# 70MHz_DDS_generator.net
KiCad netlist of a schematic drawn in EAGLE
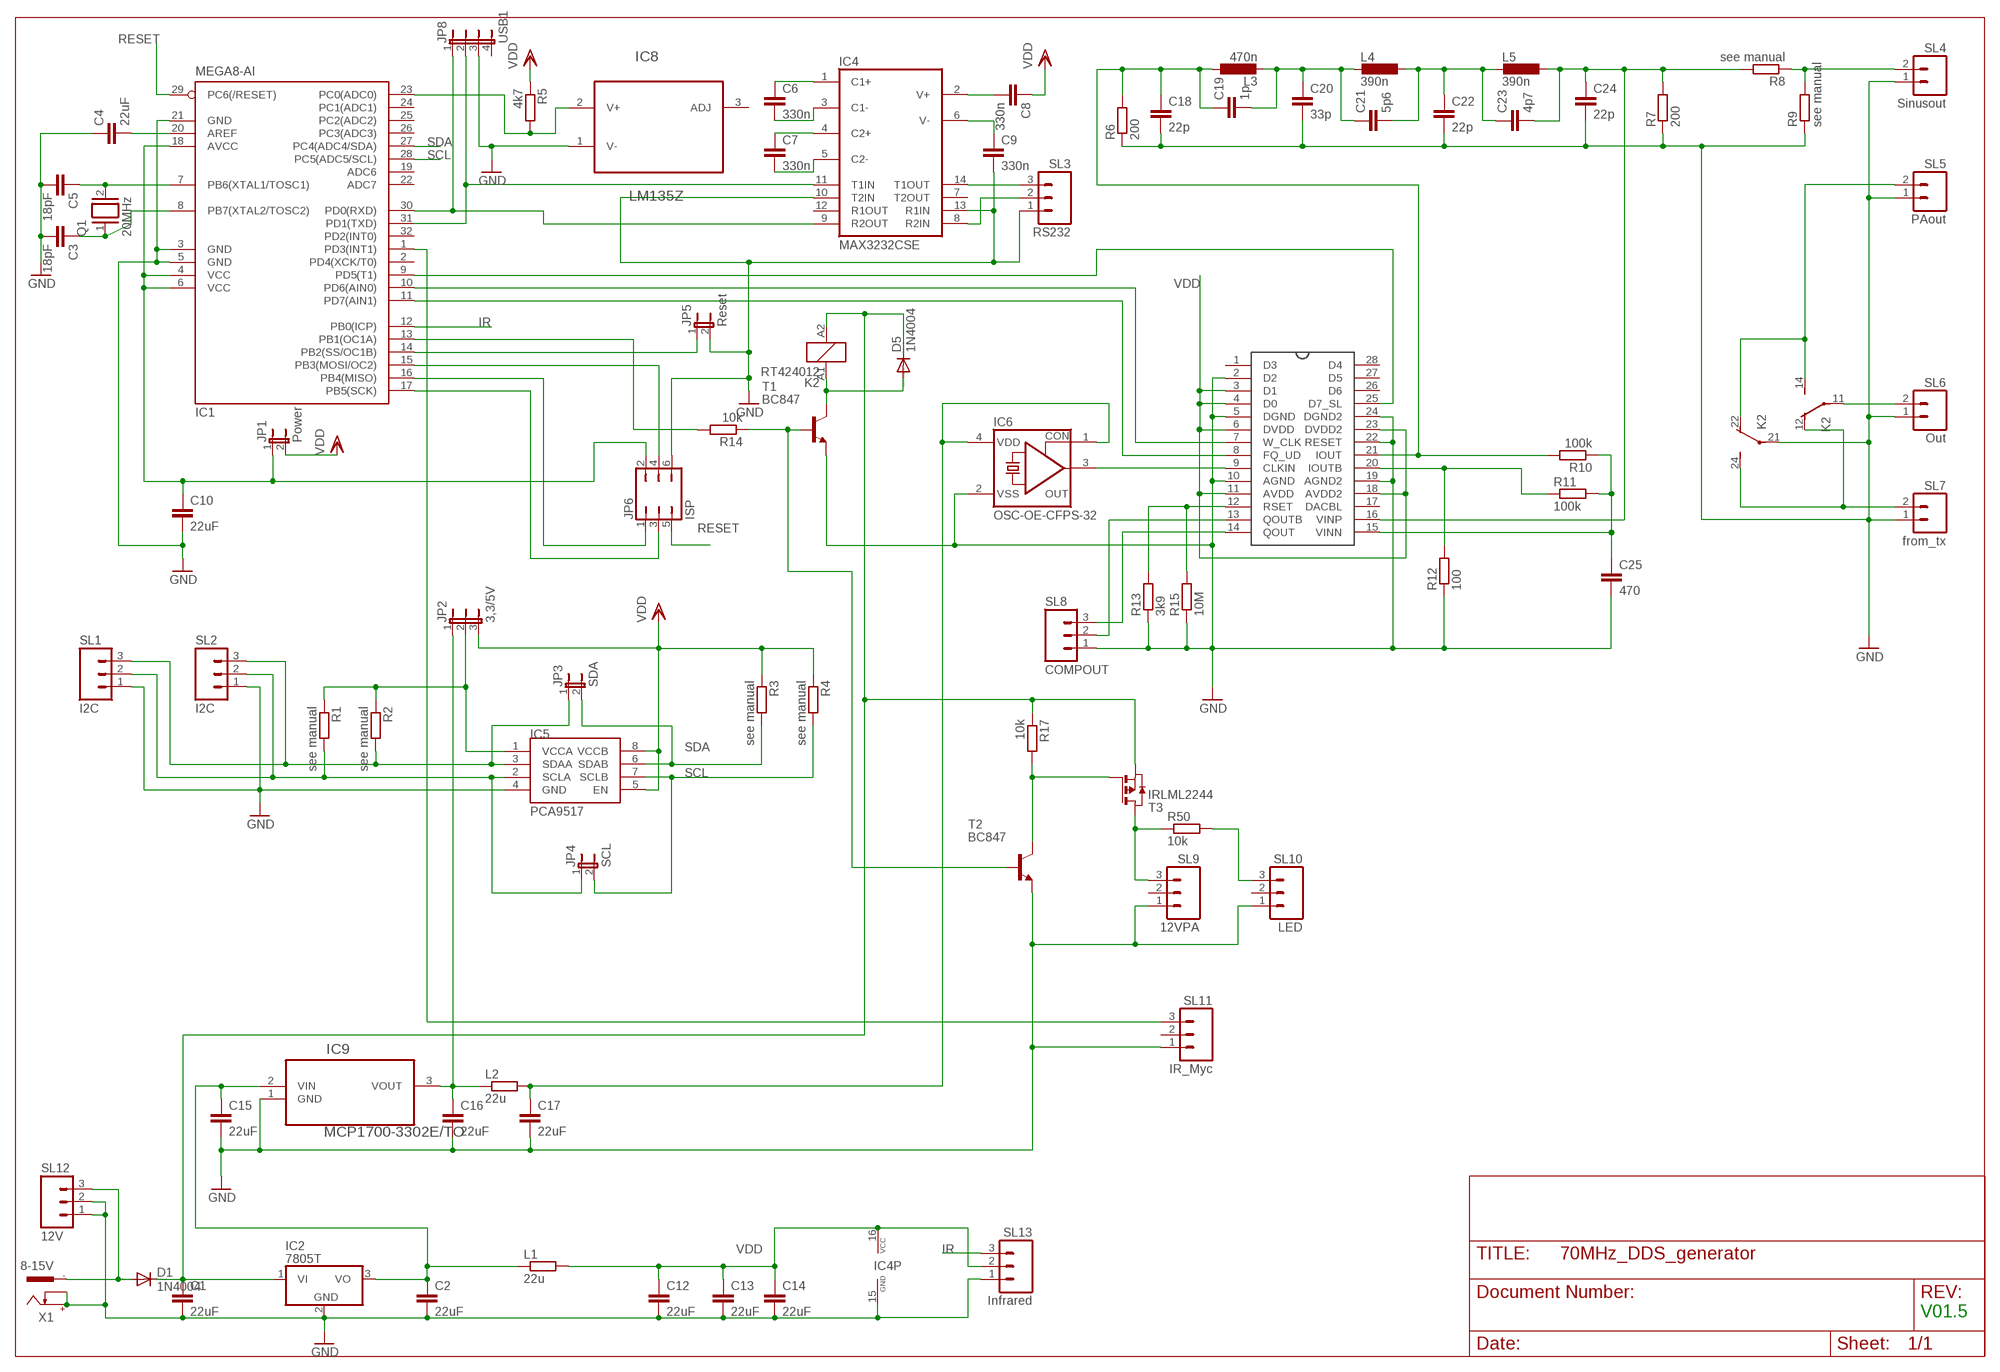
[diagram p0: schematic, sheet 1]

(export (version "E")
  (design (tool "Eeschema 10.0.6"))
  (components
    (comp (ref "C1")
      (value "22uF")
      (footprint "eagle-import:C1206")
      (libsource (lib "eagle-import") (part "C-EUC1206"))
    )
    (comp (ref "C2")
      (value "22uF")
      (footprint "eagle-import:C1206")
      (libsource (lib "eagle-import") (part "C-EUC1206"))
    )
    (comp (ref "C3")
      (value "18pF")
      (footprint "eagle-import:C025-025X050")
      (libsource (lib "eagle-import") (part "resistor_C-EU025-025X050"))
    )
    (comp (ref "C4")
      (value "22uF")
      (footprint "eagle-import:C1206")
      (libsource (lib "eagle-import") (part "C-EUC1206"))
    )
    (comp (ref "C5")
      (value "18pF")
      (footprint "eagle-import:C025-025X050")
      (libsource (lib "eagle-import") (part "resistor_C-EU025-025X050"))
    )
    (comp (ref "C6")
      (value "330n")
      (footprint "eagle-import:C1206")
      (libsource (lib "eagle-import") (part "C-EUC1206"))
    )
    (comp (ref "C7")
      (value "330n")
      (footprint "eagle-import:C1206")
      (libsource (lib "eagle-import") (part "C-EUC1206"))
    )
    (comp (ref "C8")
      (value "330n")
      (footprint "eagle-import:C1206")
      (libsource (lib "eagle-import") (part "C-EUC1206"))
    )
    (comp (ref "C9")
      (value "330n")
      (footprint "eagle-import:C1206")
      (libsource (lib "eagle-import") (part "C-EUC1206"))
    )
    (comp (ref "C10")
      (value "22uF")
      (footprint "eagle-import:C1206")
      (libsource (lib "eagle-import") (part "C-EUC1206"))
    )
    (comp (ref "C12")
      (value "22uF")
      (footprint "eagle-import:C1206")
      (libsource (lib "eagle-import") (part "C-EUC1206"))
    )
    (comp (ref "C13")
      (value "22uF")
      (footprint "eagle-import:C1206")
      (libsource (lib "eagle-import") (part "C-EUC1206"))
    )
    (comp (ref "C14")
      (value "22uF")
      (footprint "eagle-import:C1206")
      (libsource (lib "eagle-import") (part "C-EUC1206"))
    )
    (comp (ref "C15")
      (value "22uF")
      (footprint "eagle-import:C1206")
      (libsource (lib "eagle-import") (part "C-EUC1206"))
    )
    (comp (ref "C16")
      (value "22uF")
      (footprint "eagle-import:C1206")
      (libsource (lib "eagle-import") (part "C-EUC1206"))
    )
    (comp (ref "C17")
      (value "22uF")
      (footprint "eagle-import:C1206")
      (libsource (lib "eagle-import") (part "C-EUC1206"))
    )
    (comp (ref "C18")
      (value "22p")
      (footprint "eagle-import:C0805K")
      (libsource (lib "eagle-import") (part "C-EUC0805K"))
    )
    (comp (ref "C19")
      (value "1p")
      (footprint "eagle-import:C0805K")
      (libsource (lib "eagle-import") (part "C-EUC0805K"))
    )
    (comp (ref "C20")
      (value "33p")
      (footprint "eagle-import:C0805K")
      (libsource (lib "eagle-import") (part "C-EUC0805K"))
    )
    (comp (ref "C21")
      (value "5p6")
      (footprint "eagle-import:C0805K")
      (libsource (lib "eagle-import") (part "C-EUC0805K"))
    )
    (comp (ref "C22")
      (value "22p")
      (footprint "eagle-import:C0805K")
      (libsource (lib "eagle-import") (part "C-EUC0805K"))
    )
    (comp (ref "C23")
      (value "4p7")
      (footprint "eagle-import:C0805K")
      (libsource (lib "eagle-import") (part "C-EUC0805K"))
    )
    (comp (ref "C24")
      (value "22p")
      (footprint "eagle-import:C0805K")
      (libsource (lib "eagle-import") (part "C-EUC0805K"))
    )
    (comp (ref "C25")
      (value "470")
      (footprint "eagle-import:C1206")
      (libsource (lib "eagle-import") (part "C-EUC1206"))
    )
    (comp (ref "D1")
      (value "1N4004")
      (footprint "eagle-import:DO41-10")
      (libsource (lib "eagle-import") (part "1N4004"))
    )
    (comp (ref "D5")
      (value "1N4004")
      (footprint "eagle-import:DO41-10")
      (libsource (lib "eagle-import") (part "1N4004"))
    )
    (comp (ref "IC1")
      (value "MEGA8-AI")
      (footprint "eagle-import:TQFP32-08")
      (fields (field (name "MPN") "ATMEGA8-16AU"))
      (libsource (lib "eagle-import") (part "MEGA8-AI"))
    )
    (comp (ref "IC2")
      (value "7805T")
      (footprint "eagle-import:TO220H")
      (libsource (lib "eagle-import") (part "78T05"))
    )
    (comp (ref "IC4")
      (value "MAX3232CSE")
      (footprint "eagle-import:SO16")
      (libsource (lib "eagle-import") (part "MAX3232SEC"))
    )
    (comp (ref "IC5")
      (value "PCA9517")
      (footprint "eagle-import:SO-08")
      (libsource (lib "eagle-import") (part "PCA9517"))
    )
    (comp (ref "IC6")
      (value "OSC-OE-CFPS-32")
      (footprint "eagle-import:7.2X5.2-4-PAD")
      (libsource (lib "eagle-import") (part "OSC-OE-CFPS-32"))
    )
    (comp (ref "IC7")
      (value "AD9851")
      (footprint "eagle-import:SSOP28")
      (fields (field (name "MF") "Analog Devices") (field (name "MP") "AD9850"))
      (libsource (lib "eagle-import") (part "AD9850"))
    )
    (comp (ref "IC8")
      (value "LM135Z")
      (footprint "eagle-import:TO127P254X533-3P")
      (fields (field (name "MF") "STMicroelectronics"))
      (libsource (lib "eagle-import") (part "LM135Z"))
    )
    (comp (ref "IC9")
      (value "MCP1700-3302E/TO")
      (footprint "eagle-import:TO127P254X495-3")
      (fields (field (name "MF") "Microchip") (field (name "MP") "MCP1700-2702E/TO"))
      (libsource (lib "eagle-import") (part "MCP1700-2702E/TO"))
    )
    (comp (ref "JP1")
      (value "Power")
      (footprint "eagle-import:JP1")
      (libsource (lib "eagle-import") (part "JP1E"))
    )
    (comp (ref "JP2")
      (value "3,3/5V")
      (footprint "eagle-import:JP2")
      (libsource (lib "eagle-import") (part "JP2E"))
    )
    (comp (ref "JP3")
      (value "SDA")
      (footprint "eagle-import:JP1")
      (libsource (lib "eagle-import") (part "JP1E"))
    )
    (comp (ref "JP4")
      (value "SCL")
      (footprint "eagle-import:JP1")
      (libsource (lib "eagle-import") (part "JP1E"))
    )
    (comp (ref "JP5")
      (value "Reset")
      (footprint "eagle-import:JP1")
      (libsource (lib "eagle-import") (part "JP1E"))
    )
    (comp (ref "JP6")
      (value "ISP")
      (footprint "eagle-import:JP3Q")
      (libsource (lib "eagle-import") (part "JP3Q"))
    )
    (comp (ref "JP8")
      (value "USB1")
      (footprint "eagle-import:JP4")
      (libsource (lib "eagle-import") (part "JP4E"))
    )
    (comp (ref "K2")
      (value "RT424012")
      (footprint "eagle-import:RT2C_O")
      (libsource (lib "eagle-import") (part "RT42?4012"))
    )
    (comp (ref "L1")
      (value "22u")
      (footprint "eagle-import:R6332")
      (libsource (lib "eagle-import") (part "resistor_R-EU_R6332"))
    )
    (comp (ref "L2")
      (value "22u")
      (footprint "eagle-import:R6332")
      (libsource (lib "eagle-import") (part "resistor_R-EU_R6332"))
    )
    (comp (ref "L3")
      (value "470n")
      (footprint "eagle-import:L4532M")
      (libsource (lib "eagle-import") (part "L-EUL4532C"))
    )
    (comp (ref "L4")
      (value "390n")
      (footprint "eagle-import:L4532M")
      (libsource (lib "eagle-import") (part "L-EUL4532C"))
    )
    (comp (ref "L5")
      (value "390n")
      (footprint "eagle-import:L4532M")
      (libsource (lib "eagle-import") (part "L-EUL4532C"))
    )
    (comp (ref "Q1")
      (value "20MHz")
      (footprint "eagle-import:QS")
      (libsource (lib "eagle-import") (part "XTAL/S"))
    )
    (comp (ref "R1")
      (value "see manual")
      (footprint "eagle-import:R1206")
      (libsource (lib "eagle-import") (part "resistor_R-EU_R1206"))
    )
    (comp (ref "R2")
      (value "see manual")
      (footprint "eagle-import:R1206")
      (libsource (lib "eagle-import") (part "resistor_R-EU_R1206"))
    )
    (comp (ref "R3")
      (value "see manual")
      (footprint "eagle-import:R1206")
      (libsource (lib "eagle-import") (part "resistor_R-EU_R1206"))
    )
    (comp (ref "R4")
      (value "see manual")
      (footprint "eagle-import:R1206")
      (libsource (lib "eagle-import") (part "resistor_R-EU_R1206"))
    )
    (comp (ref "R5")
      (value "4k7")
      (footprint "eagle-import:R1206")
      (libsource (lib "eagle-import") (part "R-EU_R1206"))
    )
    (comp (ref "R6")
      (value "200")
      (footprint "eagle-import:R1206")
      (libsource (lib "eagle-import") (part "R-EU_R1206"))
    )
    (comp (ref "R7")
      (value "200")
      (footprint "eagle-import:R1206")
      (libsource (lib "eagle-import") (part "R-EU_R1206"))
    )
    (comp (ref "R8")
      (value "see manual")
      (footprint "eagle-import:R1206")
      (libsource (lib "eagle-import") (part "R-EU_R1206"))
    )
    (comp (ref "R9")
      (value "see manual")
      (footprint "eagle-import:R1206")
      (libsource (lib "eagle-import") (part "R-EU_R1206"))
    )
    (comp (ref "R10")
      (value "100k")
      (footprint "eagle-import:R1206")
      (libsource (lib "eagle-import") (part "R-EU_R1206"))
    )
    (comp (ref "R11")
      (value "100k")
      (footprint "eagle-import:R1206")
      (libsource (lib "eagle-import") (part "R-EU_R1206"))
    )
    (comp (ref "R12")
      (value "100")
      (footprint "eagle-import:R1206")
      (libsource (lib "eagle-import") (part "R-EU_R1206"))
    )
    (comp (ref "R13")
      (value "3k9")
      (footprint "eagle-import:R1206")
      (libsource (lib "eagle-import") (part "R-EU_R1206"))
    )
    (comp (ref "R14")
      (value "10k")
      (footprint "eagle-import:R1206")
      (libsource (lib "eagle-import") (part "R-EU_R1206"))
    )
    (comp (ref "R15")
      (value "10M")
      (footprint "eagle-import:R1206")
      (libsource (lib "eagle-import") (part "R-EU_R1206"))
    )
    (comp (ref "R17")
      (value "10k")
      (footprint "eagle-import:R1206")
      (libsource (lib "eagle-import") (part "resistor_R-EU_R1206"))
    )
    (comp (ref "R50")
      (value "10k")
      (footprint "eagle-import:R1206")
      (libsource (lib "eagle-import") (part "resistor_R-EU_R1206"))
    )
    (comp (ref "SL1")
      (value "I2C")
      (footprint "eagle-import:03P")
      (libsource (lib "eagle-import") (part "M03"))
    )
    (comp (ref "SL2")
      (value "I2C")
      (footprint "eagle-import:03P")
      (libsource (lib "eagle-import") (part "M03"))
    )
    (comp (ref "SL3")
      (value "RS232")
      (footprint "eagle-import:03P")
      (libsource (lib "eagle-import") (part "M03"))
    )
    (comp (ref "SL4")
      (value "Sinusout")
      (footprint "eagle-import:02P")
      (libsource (lib "eagle-import") (part "M02"))
    )
    (comp (ref "SL5")
      (value "PAout")
      (footprint "eagle-import:02P")
      (libsource (lib "eagle-import") (part "M02"))
    )
    (comp (ref "SL6")
      (value "Out")
      (footprint "eagle-import:02P")
      (libsource (lib "eagle-import") (part "M02"))
    )
    (comp (ref "SL7")
      (value "from_tx")
      (footprint "eagle-import:02P")
      (libsource (lib "eagle-import") (part "M02"))
    )
    (comp (ref "SL8")
      (value "COMPOUT")
      (footprint "eagle-import:03P")
      (libsource (lib "eagle-import") (part "M03"))
    )
    (comp (ref "SL9")
      (value "12VPA")
      (footprint "eagle-import:03P")
      (libsource (lib "eagle-import") (part "M03"))
    )
    (comp (ref "SL10")
      (value "LED")
      (footprint "eagle-import:03P")
      (libsource (lib "eagle-import") (part "M03"))
    )
    (comp (ref "SL11")
      (value "IR_Myc")
      (footprint "eagle-import:03P")
      (libsource (lib "eagle-import") (part "M03"))
    )
    (comp (ref "SL12")
      (value "12V")
      (footprint "eagle-import:03P")
      (libsource (lib "eagle-import") (part "M03"))
    )
    (comp (ref "SL13")
      (value "Infrared")
      (footprint "eagle-import:03P")
      (libsource (lib "eagle-import") (part "M03"))
    )
    (comp (ref "T1")
      (value "BC847")
      (footprint "eagle-import:SOT23")
      (libsource (lib "eagle-import") (part "BC847"))
    )
    (comp (ref "T2")
      (value "BC847")
      (footprint "eagle-import:SOT23")
      (libsource (lib "eagle-import") (part "BC847"))
    )
    (comp (ref "T3")
      (value "IRLML2244")
      (footprint "eagle-import:SOT-23")
      (libsource (lib "eagle-import") (part "PMOSSOT23"))
    )
    (comp (ref "X1")
      (value "8-15V")
      (footprint "eagle-import:737992-5")
      (libsource (lib "eagle-import") (part "737992-55"))
    )
  )
  (nets
    (net (code "1") (name "/IR") (class "Default")
      (node (ref "IC1") (pin "12") (pinfunction "PB0(ICP)_12") (pintype "bidirectional"))
      (node (ref "SL13") (pin "3") (pinfunction "3_3") (pintype "passive"))
    )
    (net (code "2") (name "/RESET") (class "Default")
      (node (ref "IC1") (pin "29") (pinfunction "PC6(/RESET)_29") (pintype "bidirectional"))
      (node (ref "JP6") (pin "5") (pinfunction "5_5") (pintype "passive"))
    )
    (net (code "3") (name "/SCL") (class "Default")
      (node (ref "IC1") (pin "28") (pinfunction "PC5(ADC5/SCL)_28") (pintype "bidirectional"))
      (node (ref "IC5") (pin "7") (pinfunction "SCLB_7") (pintype "bidirectional"))
      (node (ref "JP4") (pin "2") (pinfunction "2_2") (pintype "passive"))
      (node (ref "R4") (pin "2") (pinfunction "2_2") (pintype "passive"))
    )
    (net (code "4") (name "/SDA") (class "Default")
      (node (ref "IC1") (pin "27") (pinfunction "PC4(ADC4/SDA)_27") (pintype "bidirectional"))
      (node (ref "IC5") (pin "6") (pinfunction "SDAB_6") (pintype "bidirectional"))
      (node (ref "JP3") (pin "2") (pinfunction "2_2") (pintype "passive"))
      (node (ref "R3") (pin "2") (pinfunction "2_2") (pintype "passive"))
    )
    (net (code "5") (name "GND") (class "Default")
      (node (ref "C1") (pin "2") (pinfunction "2_2") (pintype "passive"))
      (node (ref "C10") (pin "2") (pinfunction "2_2") (pintype "passive"))
      (node (ref "C12") (pin "2") (pinfunction "2_2") (pintype "passive"))
      (node (ref "C13") (pin "2") (pinfunction "2_2") (pintype "passive"))
      (node (ref "C14") (pin "2") (pinfunction "2_2") (pintype "passive"))
      (node (ref "C15") (pin "2") (pinfunction "2_2") (pintype "passive"))
      (node (ref "C16") (pin "2") (pinfunction "2_2") (pintype "passive"))
      (node (ref "C17") (pin "2") (pinfunction "2_2") (pintype "passive"))
      (node (ref "C18") (pin "2") (pinfunction "2_2") (pintype "passive"))
      (node (ref "C2") (pin "2") (pinfunction "2_2") (pintype "passive"))
      (node (ref "C20") (pin "2") (pinfunction "2_2") (pintype "passive"))
      (node (ref "C22") (pin "2") (pinfunction "2_2") (pintype "passive"))
      (node (ref "C24") (pin "2") (pinfunction "2_2") (pintype "passive"))
      (node (ref "C25") (pin "2") (pinfunction "2_2") (pintype "passive"))
      (node (ref "C3") (pin "2") (pinfunction "2_2") (pintype "passive"))
      (node (ref "C4") (pin "1") (pinfunction "1_1") (pintype "passive"))
      (node (ref "C5") (pin "2") (pinfunction "2_2") (pintype "passive"))
      (node (ref "C9") (pin "2") (pinfunction "2_2") (pintype "passive"))
      (node (ref "IC1") (pin "21") (pinfunction "GND_21") (pintype "power_in"))
      (node (ref "IC1") (pin "3") (pinfunction "GND_3") (pintype "power_in"))
      (node (ref "IC1") (pin "5") (pinfunction "GND_5") (pintype "power_in"))
      (node (ref "IC2") (pin "2") (pinfunction "GND_2") (pintype "passive"))
      (node (ref "IC4") (pin "10") (pinfunction "T2IN_10") (pintype "input"))
      (node (ref "IC4") (pin "13") (pinfunction "R1IN_13") (pintype "input"))
      (node (ref "IC4") (pin "15") (pinfunction "GND_15") (pintype "power_in"))
      (node (ref "IC5") (pin "4") (pinfunction "GND_4") (pintype "bidirectional"))
      (node (ref "IC6") (pin "2") (pinfunction "VSS_2") (pintype "power_in"))
      (node (ref "IC7") (pin "10") (pinfunction "AGND_10") (pintype "power_in"))
      (node (ref "IC7") (pin "19") (pinfunction "AGND2_19") (pintype "power_in"))
      (node (ref "IC7") (pin "2") (pinfunction "D2_2") (pintype "input"))
      (node (ref "IC7") (pin "22") (pinfunction "RESET_22") (pintype "input"))
      (node (ref "IC7") (pin "24") (pinfunction "DGND2_24") (pintype "power_in"))
      (node (ref "IC7") (pin "5") (pinfunction "DGND_5") (pintype "power_in"))
      (node (ref "IC8") (pin "1") (pinfunction "V-_1") (pintype "power_in"))
      (node (ref "IC9") (pin "1") (pinfunction "GND_1") (pintype "passive"))
      (node (ref "JP5") (pin "2") (pinfunction "2_2") (pintype "passive"))
      (node (ref "JP6") (pin "6") (pinfunction "6_6") (pintype "passive"))
      (node (ref "JP8") (pin "3") (pinfunction "3_3") (pintype "passive"))
      (node (ref "K2") (pin "21") (pinfunction "P_21") (pintype "passive"))
      (node (ref "R12") (pin "1") (pinfunction "1_1") (pintype "passive"))
      (node (ref "R13") (pin "1") (pinfunction "1_1") (pintype "passive"))
      (node (ref "R15") (pin "1") (pinfunction "1_1") (pintype "passive"))
      (node (ref "R6") (pin "1") (pinfunction "1_1") (pintype "passive"))
      (node (ref "R7") (pin "1") (pinfunction "1_1") (pintype "passive"))
      (node (ref "R9") (pin "1") (pinfunction "1_1") (pintype "passive"))
      (node (ref "SL1") (pin "1") (pinfunction "1_1") (pintype "passive"))
      (node (ref "SL10") (pin "1") (pinfunction "1_1") (pintype "passive"))
      (node (ref "SL11") (pin "1") (pinfunction "1_1") (pintype "passive"))
      (node (ref "SL12") (pin "1") (pinfunction "1_1") (pintype "passive"))
      (node (ref "SL12") (pin "2") (pinfunction "2_2") (pintype "passive"))
      (node (ref "SL13") (pin "1") (pinfunction "1_1") (pintype "passive"))
      (node (ref "SL2") (pin "1") (pinfunction "1_1") (pintype "passive"))
      (node (ref "SL3") (pin "1") (pinfunction "1_1") (pintype "passive"))
      (node (ref "SL4") (pin "1") (pinfunction "1_1") (pintype "passive"))
      (node (ref "SL5") (pin "1") (pinfunction "1_1") (pintype "passive"))
      (node (ref "SL6") (pin "1") (pinfunction "1_1") (pintype "passive"))
      (node (ref "SL7") (pin "1") (pinfunction "1_1") (pintype "passive"))
      (node (ref "SL8") (pin "1") (pinfunction "1_1") (pintype "passive"))
      (node (ref "SL9") (pin "1") (pinfunction "1_1") (pintype "passive"))
      (node (ref "T1") (pin "2") (pinfunction "E_2") (pintype "passive"))
      (node (ref "T2") (pin "2") (pinfunction "E_2") (pintype "passive"))
      (node (ref "X1") (pin "+") (pinfunction "+_+") (pintype "passive"))
      (node (ref "X1") (pin "K") (pinfunction "K_K") (pintype "passive"))
    )
    (net (code "6") (name "Net-(C19-Pad2)") (class "Default")
      (node (ref "C19") (pin "2") (pinfunction "2_2") (pintype "passive"))
      (node (ref "C20") (pin "1") (pinfunction "1_1") (pintype "passive"))
      (node (ref "C21") (pin "1") (pinfunction "1_1") (pintype "passive"))
      (node (ref "L3") (pin "2") (pinfunction "2_2") (pintype "passive"))
      (node (ref "L4") (pin "2") (pinfunction "2_2") (pintype "passive"))
    )
    (net (code "7") (name "Net-(C21-Pad2)") (class "Default")
      (node (ref "C21") (pin "2") (pinfunction "2_2") (pintype "passive"))
      (node (ref "C22") (pin "1") (pinfunction "1_1") (pintype "passive"))
      (node (ref "C23") (pin "1") (pinfunction "1_1") (pintype "passive"))
      (node (ref "L4") (pin "1") (pinfunction "1_1") (pintype "passive"))
      (node (ref "L5") (pin "2") (pinfunction "2_2") (pintype "passive"))
    )
    (net (code "8") (name "Net-(D1-PadA)") (class "Default")
      (node (ref "D1") (pin "A") (pinfunction "A_A") (pintype "passive"))
      (node (ref "SL12") (pin "3") (pinfunction "3_3") (pintype "passive"))
      (node (ref "X1") (pin "-1") (pinfunction "-1_-1") (pintype "passive"))
    )
    (net (code "9") (name "Net-(IC1-AREF)") (class "Default")
      (node (ref "C4") (pin "2") (pinfunction "2_2") (pintype "passive"))
      (node (ref "IC1") (pin "20") (pinfunction "AREF_20") (pintype "passive"))
    )
    (net (code "10") (name "Net-(IC1-AVCC)") (class "Default")
      (node (ref "C10") (pin "1") (pinfunction "1_1") (pintype "passive"))
      (node (ref "IC1") (pin "18") (pinfunction "AVCC_18") (pintype "power_in"))
      (node (ref "IC1") (pin "4") (pinfunction "VCC_4") (pintype "power_in"))
      (node (ref "IC1") (pin "6") (pinfunction "VCC_6") (pintype "power_in"))
      (node (ref "JP1") (pin "1") (pinfunction "1_1") (pintype "passive"))
      (node (ref "JP6") (pin "2") (pinfunction "2_2") (pintype "passive"))
    )
    (net (code "11") (name "Net-(IC1-PB1(OC1A))") (class "Default")
      (node (ref "IC1") (pin "13") (pinfunction "PB1(OC1A)_13") (pintype "bidirectional"))
      (node (ref "R14") (pin "2") (pinfunction "2_2") (pintype "passive"))
    )
    (net (code "12") (name "Net-(IC1-PB2(SS{slash}OC1B))") (class "Default")
      (node (ref "IC1") (pin "14") (pinfunction "PB2(SS/OC1B)_14") (pintype "bidirectional"))
      (node (ref "JP5") (pin "1") (pinfunction "1_1") (pintype "passive"))
    )
    (net (code "13") (name "Net-(IC1-PB3(MOSI{slash}OC2))") (class "Default")
      (node (ref "IC1") (pin "15") (pinfunction "PB3(MOSI/OC2)_15") (pintype "bidirectional"))
      (node (ref "JP6") (pin "4") (pinfunction "4_4") (pintype "passive"))
    )
    (net (code "14") (name "Net-(IC1-PB4(MISO))") (class "Default")
      (node (ref "IC1") (pin "16") (pinfunction "PB4(MISO)_16") (pintype "bidirectional"))
      (node (ref "JP6") (pin "1") (pinfunction "1_1") (pintype "passive"))
    )
    (net (code "15") (name "Net-(IC1-PB5(SCK))") (class "Default")
      (node (ref "IC1") (pin "17") (pinfunction "PB5(SCK)_17") (pintype "bidirectional"))
      (node (ref "JP6") (pin "3") (pinfunction "3_3") (pintype "passive"))
    )
    (net (code "16") (name "Net-(IC1-PB6(XTAL1{slash}TOSC1))") (class "Default")
      (node (ref "C5") (pin "1") (pinfunction "1_1") (pintype "passive"))
      (node (ref "IC1") (pin "7") (pinfunction "PB6(XTAL1/TOSC1)_7") (pintype "bidirectional"))
      (node (ref "Q1") (pin "2") (pinfunction "2_2") (pintype "passive"))
    )
    (net (code "17") (name "Net-(IC1-PB7(XTAL2{slash}TOSC2))") (class "Default")
      (node (ref "C3") (pin "1") (pinfunction "1_1") (pintype "passive"))
      (node (ref "IC1") (pin "8") (pinfunction "PB7(XTAL2/TOSC2)_8") (pintype "bidirectional"))
      (node (ref "Q1") (pin "1") (pinfunction "1_1") (pintype "passive"))
    )
    (net (code "18") (name "Net-(IC1-PC0(ADC0))") (class "Default")
      (node (ref "IC1") (pin "23") (pinfunction "PC0(ADC0)_23") (pintype "bidirectional"))
      (node (ref "IC8") (pin "2") (pinfunction "V+_2") (pintype "power_in"))
      (node (ref "R5") (pin "2") (pinfunction "2_2") (pintype "passive"))
    )
    (net (code "19") (name "Net-(IC1-PD0(RXD))") (class "Default")
      (node (ref "IC1") (pin "30") (pinfunction "PD0(RXD)_30") (pintype "bidirectional"))
      (node (ref "IC4") (pin "9") (pinfunction "R2OUT_9") (pintype "output"))
      (node (ref "JP8") (pin "1") (pinfunction "1_1") (pintype "passive"))
    )
    (net (code "20") (name "Net-(IC1-PD1(TXD))") (class "Default")
      (node (ref "IC1") (pin "31") (pinfunction "PD1(TXD)_31") (pintype "bidirectional"))
      (node (ref "IC4") (pin "11") (pinfunction "T1IN_11") (pintype "input"))
      (node (ref "JP8") (pin "2") (pinfunction "2_2") (pintype "passive"))
    )
    (net (code "21") (name "Net-(IC1-PD3(INT1))") (class "Default")
      (node (ref "IC1") (pin "1") (pinfunction "PD3(INT1)_1") (pintype "bidirectional"))
      (node (ref "SL11") (pin "3") (pinfunction "3_3") (pintype "passive"))
    )
    (net (code "22") (name "Net-(IC1-PD5(T1))") (class "Default")
      (node (ref "IC1") (pin "9") (pinfunction "PD5(T1)_9") (pintype "bidirectional"))
      (node (ref "IC7") (pin "25") (pinfunction "D7_SL_25") (pintype "input"))
    )
    (net (code "23") (name "Net-(IC1-PD6(AIN0))") (class "Default")
      (node (ref "IC1") (pin "10") (pinfunction "PD6(AIN0)_10") (pintype "bidirectional"))
      (node (ref "IC7") (pin "7") (pinfunction "W_CLK_7") (pintype "bidirectional"))
    )
    (net (code "24") (name "Net-(IC1-PD7(AIN1))") (class "Default")
      (node (ref "IC1") (pin "11") (pinfunction "PD7(AIN1)_11") (pintype "bidirectional"))
      (node (ref "IC7") (pin "8") (pinfunction "FQ_UD_8") (pintype "bidirectional"))
    )
    (net (code "25") (name "Net-(IC2-VI)") (class "Default")
      (node (ref "C1") (pin "1") (pinfunction "1_1") (pintype "passive"))
      (node (ref "D1") (pin "C") (pinfunction "C_C") (pintype "passive"))
      (node (ref "D5") (pin "C") (pinfunction "C_C") (pintype "passive"))
      (node (ref "IC2") (pin "1") (pinfunction "VI_1") (pintype "input"))
      (node (ref "K2") (pin "A2") (pinfunction "2_A2") (pintype "passive"))
      (node (ref "R17") (pin "1") (pinfunction "1_1") (pintype "passive"))
      (node (ref "T3") (pin "2") (pinfunction "S_2") (pintype "passive"))
    )
    (net (code "26") (name "Net-(IC2-VO)") (class "Default")
      (node (ref "C15") (pin "1") (pinfunction "1_1") (pintype "passive"))
      (node (ref "C2") (pin "1") (pinfunction "1_1") (pintype "passive"))
      (node (ref "IC2") (pin "3") (pinfunction "VO_3") (pintype "passive"))
      (node (ref "IC9") (pin "2") (pinfunction "VIN_2") (pintype "input"))
      (node (ref "L1") (pin "1") (pinfunction "1_1") (pintype "passive"))
    )
    (net (code "27") (name "Net-(IC4A-C1+)") (class "Default")
      (node (ref "C6") (pin "1") (pinfunction "1_1") (pintype "passive"))
      (node (ref "IC4") (pin "1") (pinfunction "C1+_1") (pintype "bidirectional"))
    )
    (net (code "28") (name "Net-(IC4A-C1-)") (class "Default")
      (node (ref "C6") (pin "2") (pinfunction "2_2") (pintype "passive"))
      (node (ref "IC4") (pin "3") (pinfunction "C1-_3") (pintype "bidirectional"))
    )
    (net (code "29") (name "Net-(IC4A-C2+)") (class "Default")
      (node (ref "C7") (pin "1") (pinfunction "1_1") (pintype "passive"))
      (node (ref "IC4") (pin "4") (pinfunction "C2+_4") (pintype "bidirectional"))
    )
    (net (code "30") (name "Net-(IC4A-C2-)") (class "Default")
      (node (ref "C7") (pin "2") (pinfunction "2_2") (pintype "passive"))
      (node (ref "IC4") (pin "5") (pinfunction "C2-_5") (pintype "bidirectional"))
    )
    (net (code "31") (name "Net-(IC4A-R2IN)") (class "Default")
      (node (ref "IC4") (pin "8") (pinfunction "R2IN_8") (pintype "input"))
      (node (ref "SL3") (pin "2") (pinfunction "2_2") (pintype "passive"))
    )
    (net (code "32") (name "Net-(IC4A-T1OUT)") (class "Default")
      (node (ref "IC4") (pin "14") (pinfunction "T1OUT_14") (pintype "output"))
      (node (ref "SL3") (pin "3") (pinfunction "3_3") (pintype "passive"))
    )
    (net (code "33") (name "Net-(IC4A-V+)") (class "Default")
      (node (ref "C8") (pin "2") (pinfunction "2_2") (pintype "passive"))
      (node (ref "IC4") (pin "2") (pinfunction "V+_2") (pintype "bidirectional"))
    )
    (net (code "34") (name "Net-(IC4A-V-)") (class "Default")
      (node (ref "C9") (pin "1") (pinfunction "1_1") (pintype "passive"))
      (node (ref "IC4") (pin "6") (pinfunction "V-_6") (pintype "bidirectional"))
    )
    (net (code "35") (name "Net-(IC5-SCLA)") (class "Default")
      (node (ref "IC5") (pin "2") (pinfunction "SCLA_2") (pintype "bidirectional"))
      (node (ref "JP4") (pin "1") (pinfunction "1_1") (pintype "passive"))
      (node (ref "R1") (pin "2") (pinfunction "2_2") (pintype "passive"))
      (node (ref "SL1") (pin "2") (pinfunction "2_2") (pintype "passive"))
      (node (ref "SL2") (pin "2") (pinfunction "2_2") (pintype "passive"))
    )
    (net (code "36") (name "Net-(IC5-SDAA)") (class "Default")
      (node (ref "IC5") (pin "3") (pinfunction "SDAA_3") (pintype "bidirectional"))
      (node (ref "JP3") (pin "1") (pinfunction "1_1") (pintype "passive"))
      (node (ref "R2") (pin "2") (pinfunction "2_2") (pintype "passive"))
      (node (ref "SL1") (pin "3") (pinfunction "3_3") (pintype "passive"))
      (node (ref "SL2") (pin "3") (pinfunction "3_3") (pintype "passive"))
    )
    (net (code "37") (name "Net-(IC5-VCCA)") (class "Default")
      (node (ref "IC5") (pin "1") (pinfunction "VCCA_1") (pintype "bidirectional"))
      (node (ref "JP2") (pin "2") (pinfunction "2_2") (pintype "passive"))
      (node (ref "R1") (pin "1") (pinfunction "1_1") (pintype "passive"))
      (node (ref "R2") (pin "1") (pinfunction "1_1") (pintype "passive"))
    )
    (net (code "38") (name "Net-(IC6-CON)") (class "Default")
      (node (ref "C17") (pin "1") (pinfunction "1_1") (pintype "passive"))
      (node (ref "IC6") (pin "1") (pinfunction "CON_1") (pintype "input"))
      (node (ref "IC6") (pin "4") (pinfunction "VDD_4") (pintype "power_in"))
      (node (ref "L2") (pin "2") (pinfunction "2_2") (pintype "passive"))
    )
    (net (code "39") (name "Net-(IC6-OUT)") (class "Default")
      (node (ref "IC6") (pin "3") (pinfunction "OUT_3") (pintype "output"))
      (node (ref "IC7") (pin "9") (pinfunction "CLKIN_9") (pintype "input"))
    )
    (net (code "40") (name "Net-(IC7-IOUT)") (class "Default")
      (node (ref "C18") (pin "1") (pinfunction "1_1") (pintype "passive"))
      (node (ref "C19") (pin "1") (pinfunction "1_1") (pintype "passive"))
      (node (ref "IC7") (pin "21") (pinfunction "IOUT_21") (pintype "output"))
      (node (ref "L3") (pin "1") (pinfunction "1_1") (pintype "passive"))
      (node (ref "R10") (pin "2") (pinfunction "2_2") (pintype "passive"))
      (node (ref "R6") (pin "2") (pinfunction "2_2") (pintype "passive"))
    )
    (net (code "41") (name "Net-(IC7-IOUTB)") (class "Default")
      (node (ref "IC7") (pin "20") (pinfunction "IOUTB_20") (pintype "output"))
      (node (ref "R11") (pin "1") (pinfunction "1_1") (pintype "passive"))
      (node (ref "R12") (pin "2") (pinfunction "2_2") (pintype "passive"))
    )
    (net (code "42") (name "Net-(IC7-QOUT)") (class "Default")
      (node (ref "IC7") (pin "14") (pinfunction "QOUT_14") (pintype "output"))
      (node (ref "SL8") (pin "3") (pinfunction "3_3") (pintype "passive"))
    )
    (net (code "43") (name "Net-(IC7-QOUTB)") (class "Default")
      (node (ref "IC7") (pin "13") (pinfunction "QOUTB_13") (pintype "output"))
      (node (ref "SL8") (pin "2") (pinfunction "2_2") (pintype "passive"))
    )
    (net (code "44") (name "Net-(IC7-RSET)") (class "Default")
      (node (ref "IC7") (pin "12") (pinfunction "RSET_12") (pintype "input"))
      (node (ref "R13") (pin "2") (pinfunction "2_2") (pintype "passive"))
      (node (ref "R15") (pin "2") (pinfunction "2_2") (pintype "passive"))
    )
    (net (code "45") (name "Net-(IC7-VINN)") (class "Default")
      (node (ref "C25") (pin "1") (pinfunction "1_1") (pintype "passive"))
      (node (ref "IC7") (pin "15") (pinfunction "VINN_15") (pintype "input"))
      (node (ref "R10") (pin "1") (pinfunction "1_1") (pintype "passive"))
      (node (ref "R11") (pin "2") (pinfunction "2_2") (pintype "passive"))
    )
    (net (code "46") (name "Net-(IC7-VINP)") (class "Default")
      (node (ref "C23") (pin "2") (pinfunction "2_2") (pintype "passive"))
      (node (ref "C24") (pin "1") (pinfunction "1_1") (pintype "passive"))
      (node (ref "IC7") (pin "16") (pinfunction "VINP_16") (pintype "input"))
      (node (ref "L5") (pin "1") (pinfunction "1_1") (pintype "passive"))
      (node (ref "R7") (pin "2") (pinfunction "2_2") (pintype "passive"))
      (node (ref "R8") (pin "2") (pinfunction "2_2") (pintype "passive"))
    )
    (net (code "47") (name "Net-(IC9-VOUT)") (class "Default")
      (node (ref "C16") (pin "1") (pinfunction "1_1") (pintype "passive"))
      (node (ref "IC9") (pin "3") (pinfunction "VOUT_3") (pintype "output"))
      (node (ref "JP2") (pin "1") (pinfunction "1_1") (pintype "passive"))
      (node (ref "L2") (pin "1") (pinfunction "1_1") (pintype "passive"))
    )
    (net (code "48") (name "Net-(K2A-1)") (class "Default")
      (node (ref "D5") (pin "A") (pinfunction "A_A") (pintype "passive"))
      (node (ref "K2") (pin "A1") (pinfunction "1_A1") (pintype "passive"))
      (node (ref "T1") (pin "3") (pinfunction "C_3") (pintype "passive"))
    )
    (net (code "49") (name "Net-(K2B-O)") (class "Default")
      (node (ref "K2") (pin "12") (pinfunction "O_12") (pintype "passive"))
      (node (ref "K2") (pin "24") (pinfunction "S_24") (pintype "passive"))
      (node (ref "SL7") (pin "2") (pinfunction "2_2") (pintype "passive"))
    )
    (net (code "50") (name "Net-(K2B-P)") (class "Default")
      (node (ref "K2") (pin "11") (pinfunction "P_11") (pintype "passive"))
      (node (ref "SL6") (pin "2") (pinfunction "2_2") (pintype "passive"))
    )
    (net (code "51") (name "Net-(K2B-S)") (class "Default")
      (node (ref "K2") (pin "14") (pinfunction "S_14") (pintype "passive"))
      (node (ref "K2") (pin "22") (pinfunction "O_22") (pintype "passive"))
      (node (ref "SL5") (pin "2") (pinfunction "2_2") (pintype "passive"))
    )
    (net (code "52") (name "Net-(R8-Pad1)") (class "Default")
      (node (ref "R8") (pin "1") (pinfunction "1_1") (pintype "passive"))
      (node (ref "R9") (pin "2") (pinfunction "2_2") (pintype "passive"))
      (node (ref "SL4") (pin "2") (pinfunction "2_2") (pintype "passive"))
    )
    (net (code "53") (name "Net-(R50-Pad2)") (class "Default")
      (node (ref "R50") (pin "2") (pinfunction "2_2") (pintype "passive"))
      (node (ref "SL10") (pin "3") (pinfunction "3_3") (pintype "passive"))
    )
    (net (code "54") (name "Net-(T1-B)") (class "Default")
      (node (ref "R14") (pin "1") (pinfunction "1_1") (pintype "passive"))
      (node (ref "T1") (pin "1") (pinfunction "B_1") (pintype "passive"))
      (node (ref "T2") (pin "1") (pinfunction "B_1") (pintype "passive"))
    )
    (net (code "55") (name "Net-(T2-C)") (class "Default")
      (node (ref "R17") (pin "2") (pinfunction "2_2") (pintype "passive"))
      (node (ref "T2") (pin "3") (pinfunction "C_3") (pintype "passive"))
      (node (ref "T3") (pin "3") (pinfunction "G_3") (pintype "passive"))
    )
    (net (code "56") (name "Net-(T3-D)") (class "Default")
      (node (ref "R50") (pin "1") (pinfunction "1_1") (pintype "passive"))
      (node (ref "SL9") (pin "3") (pinfunction "3_3") (pintype "passive"))
      (node (ref "T3") (pin "1") (pinfunction "D_1") (pintype "passive"))
    )
    (net (code "57") (name "VDD") (class "Default")
      (node (ref "C12") (pin "1") (pinfunction "1_1") (pintype "passive"))
      (node (ref "C13") (pin "1") (pinfunction "1_1") (pintype "passive"))
      (node (ref "C14") (pin "1") (pinfunction "1_1") (pintype "passive"))
      (node (ref "C8") (pin "1") (pinfunction "1_1") (pintype "passive"))
      (node (ref "IC4") (pin "16") (pinfunction "VCC_16") (pintype "power_in"))
      (node (ref "IC5") (pin "5") (pinfunction "EN_5") (pintype "bidirectional"))
      (node (ref "IC5") (pin "8") (pinfunction "VCCB_8") (pintype "bidirectional"))
      (node (ref "IC7") (pin "11") (pinfunction "AVDD_11") (pintype "power_in"))
      (node (ref "IC7") (pin "18") (pinfunction "AVDD2_18") (pintype "power_in"))
      (node (ref "IC7") (pin "23") (pinfunction "DVDD2_23") (pintype "power_in"))
      (node (ref "IC7") (pin "3") (pinfunction "D1_3") (pintype "input"))
      (node (ref "IC7") (pin "4") (pinfunction "D0_4") (pintype "bidirectional"))
      (node (ref "IC7") (pin "6") (pinfunction "DVDD_6") (pintype "power_in"))
      (node (ref "JP1") (pin "2") (pinfunction "2_2") (pintype "passive"))
      (node (ref "JP2") (pin "3") (pinfunction "3_3") (pintype "passive"))
      (node (ref "L1") (pin "2") (pinfunction "2_2") (pintype "passive"))
      (node (ref "R3") (pin "1") (pinfunction "1_1") (pintype "passive"))
      (node (ref "R4") (pin "1") (pinfunction "1_1") (pintype "passive"))
      (node (ref "R5") (pin "1") (pinfunction "1_1") (pintype "passive"))
      (node (ref "SL13") (pin "2") (pinfunction "2_2") (pintype "passive"))
    )
    (net (code "58") (name "unconnected-(IC1-ADC6-Pad19)") (class "Default")
      (node (ref "IC1") (pin "19") (pinfunction "ADC6_19") (pintype "bidirectional"))
    )
    (net (code "59") (name "unconnected-(IC1-ADC7-Pad22)") (class "Default")
      (node (ref "IC1") (pin "22") (pinfunction "ADC7_22") (pintype "bidirectional"))
    )
    (net (code "60") (name "unconnected-(IC1-PC1(ADC1)-Pad24)") (class "Default")
      (node (ref "IC1") (pin "24") (pinfunction "PC1(ADC1)_24") (pintype "bidirectional"))
    )
    (net (code "61") (name "unconnected-(IC1-PC2(ADC2)-Pad25)") (class "Default")
      (node (ref "IC1") (pin "25") (pinfunction "PC2(ADC2)_25") (pintype "bidirectional"))
    )
    (net (code "62") (name "unconnected-(IC1-PC3(ADC3)-Pad26)") (class "Default")
      (node (ref "IC1") (pin "26") (pinfunction "PC3(ADC3)_26") (pintype "bidirectional"))
    )
    (net (code "63") (name "unconnected-(IC1-PD2(INT0)-Pad32)") (class "Default")
      (node (ref "IC1") (pin "32") (pinfunction "PD2(INT0)_32") (pintype "bidirectional"))
    )
    (net (code "64") (name "unconnected-(IC1-PD4(XCK{slash}T0)-Pad2)") (class "Default")
      (node (ref "IC1") (pin "2") (pinfunction "PD4(XCK/T0)_2") (pintype "bidirectional"))
    )
    (net (code "65") (name "unconnected-(IC4A-R1OUT-Pad12)") (class "Default")
      (node (ref "IC4") (pin "12") (pinfunction "R1OUT_12") (pintype "output"))
    )
    (net (code "66") (name "unconnected-(IC4A-T2OUT-Pad7)") (class "Default")
      (node (ref "IC4") (pin "7") (pinfunction "T2OUT_7") (pintype "output"))
    )
    (net (code "67") (name "unconnected-(IC7-D3-Pad1)") (class "Default")
      (node (ref "IC7") (pin "1") (pinfunction "D3_1") (pintype "input"))
    )
    (net (code "68") (name "unconnected-(IC7-D4-Pad28)") (class "Default")
      (node (ref "IC7") (pin "28") (pinfunction "D4_28") (pintype "input"))
    )
    (net (code "69") (name "unconnected-(IC7-D5-Pad27)") (class "Default")
      (node (ref "IC7") (pin "27") (pinfunction "D5_27") (pintype "input"))
    )
    (net (code "70") (name "unconnected-(IC7-D6-Pad26)") (class "Default")
      (node (ref "IC7") (pin "26") (pinfunction "D6_26") (pintype "input"))
    )
    (net (code "71") (name "unconnected-(IC7-DACBL-Pad17)") (class "Default")
      (node (ref "IC7") (pin "17") (pinfunction "DACBL_17") (pintype "no_connect"))
    )
    (net (code "72") (name "unconnected-(IC8-ADJ-Pad3)") (class "Default")
      (node (ref "IC8") (pin "3") (pinfunction "ADJ_3") (pintype "input"))
    )
    (net (code "73") (name "unconnected-(JP8-Pad4)") (class "Default")
      (node (ref "JP8") (pin "4") (pinfunction "4_4") (pintype "passive"))
    )
    (net (code "74") (name "unconnected-(SL9-Pad2)") (class "Default")
      (node (ref "SL9") (pin "2") (pinfunction "2_2") (pintype "passive"))
    )
    (net (code "75") (name "unconnected-(SL10-Pad2)") (class "Default")
      (node (ref "SL10") (pin "2") (pinfunction "2_2") (pintype "passive"))
    )
    (net (code "76") (name "unconnected-(SL11-Pad2)") (class "Default")
      (node (ref "SL11") (pin "2") (pinfunction "2_2") (pintype "passive"))
    )
    (net (code "77") (name "unconnected-(X1-Pad-2)") (class "Default")
      (node (ref "X1") (pin "-2") (pinfunction "-2_-2") (pintype "passive"))
    )
  )
)
